# SI24r1.net
KiCad netlist of a schematic drawn in Altium Designer
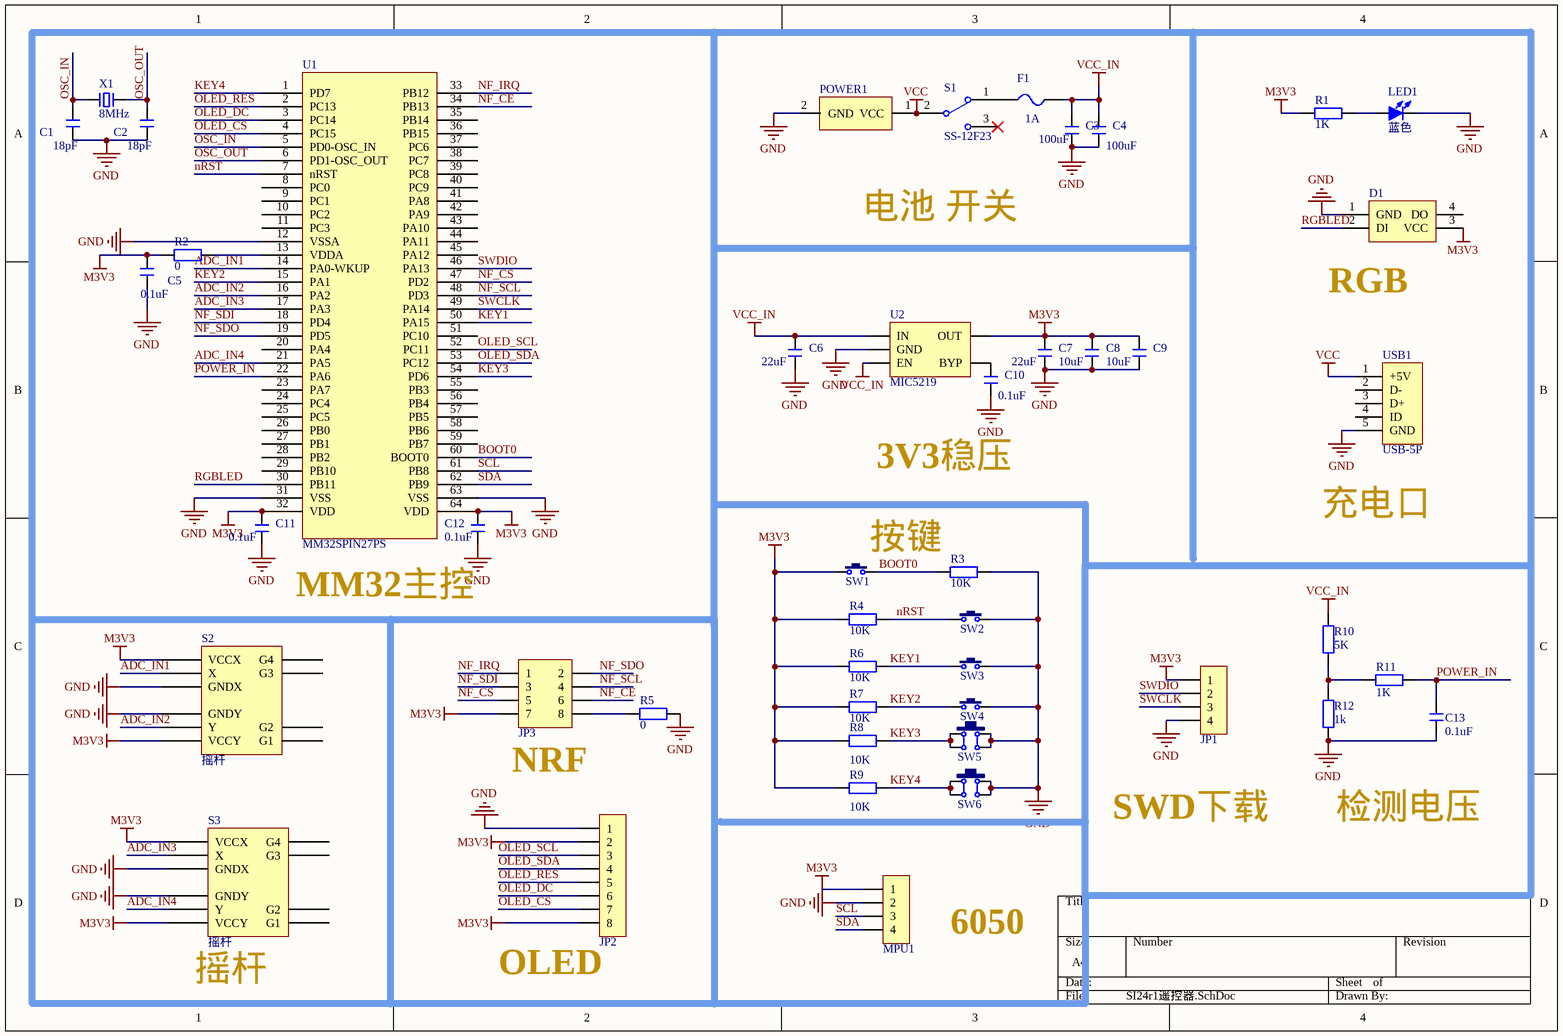
[diagram p0: SI24r1遥控器.SchDoc]

(export (version "E")
  (design (tool "Eeschema 10.0.6"))
  (components
    (comp (ref "C1")
      (value "18pF")
      (footprint "C 0805_M")
      (description "贴片电容")
      (libsource (lib "0.1 - 电阻-电容-电感") (part "C"))
    )
    (comp (ref "C2")
      (value "18pF")
      (footprint "C 0805_M")
      (description "贴片电容")
      (libsource (lib "0.1 - 电阻-电容-电感") (part "C"))
    )
    (comp (ref "C3")
      (value "100uF")
      (footprint "C 0805_M")
      (description "贴片电容")
      (libsource (lib "0.1 - 电阻-电容-电感") (part "C"))
    )
    (comp (ref "C4")
      (value "100uF")
      (footprint "C 0805_M")
      (description "贴片电容")
      (libsource (lib "0.1 - 电阻-电容-电感") (part "C"))
    )
    (comp (ref "C5")
      (value "0.1uF")
      (footprint "C 0805_M")
      (description "贴片电容")
      (libsource (lib "0.1 - 电阻-电容-电感") (part "C"))
    )
    (comp (ref "C6")
      (value "22uF")
      (footprint "C 0805_M")
      (description "贴片电容")
      (libsource (lib "0.1 - 电阻-电容-电感") (part "C"))
    )
    (comp (ref "C7")
      (value "22uF")
      (footprint "C 0805_M")
      (description "贴片电容")
      (libsource (lib "0.1 - 电阻-电容-电感") (part "C"))
    )
    (comp (ref "C8")
      (value "10uF")
      (footprint "C 0805_M")
      (description "贴片电容")
      (libsource (lib "0.1 - 电阻-电容-电感") (part "C"))
    )
    (comp (ref "C9")
      (value "10uF")
      (footprint "C 0805_M")
      (description "贴片电容")
      (libsource (lib "0.1 - 电阻-电容-电感") (part "C"))
    )
    (comp (ref "C10")
      (value "0.1uF")
      (footprint "C 0805_M")
      (description "贴片电容")
      (libsource (lib "0.1 - 电阻-电容-电感") (part "C"))
    )
    (comp (ref "C11")
      (value "0.1uF")
      (footprint "C 0805_M")
      (description "贴片电容")
      (libsource (lib "0.1 - 电阻-电容-电感") (part "C"))
    )
    (comp (ref "C12")
      (value "0.1uF")
      (footprint "C 0805_M")
      (description "贴片电容")
      (libsource (lib "0.1 - 电阻-电容-电感") (part "C"))
    )
    (comp (ref "C13")
      (value "0.1uF")
      (footprint "C 0805_M")
      (description "贴片电容")
      (libsource (lib "0.1 - 电阻-电容-电感") (part "C"))
    )
    (comp (ref "D1")
      (value "P923D")
      (footprint "RGB_LED_5050")
      (fields (field (name "PUBLISHER") "mazhongwei"))
      (libsource (lib "RoboFly") (part "P923D"))
    )
    (comp (ref "F1")
      (value "1A")
      (footprint "FU 0805")
      (description "贴片保险丝")
      (fields (field (name "版权归属") "源创客"))
      (libsource (lib "2.0 - 保险丝-晶振-光耦") (part "FU"))
    )
    (comp (ref "JP1")
      (value "HDR-1X4")
      (footprint "XH2.54-WI-4P")
      (description "4P接插件")
      (fields (field (name "版权归属") "封装库来自淘宝 ID：黄晶宝石"))
      (libsource (lib "5.3 - 接插件-脚距2.54 (100mil) ") (part "Header 4"))
    )
    (comp (ref "JP2")
      (value "HDR-1X8")
      (footprint "IPS")
      (description "8P接插件")
      (fields (field (name "版权归属") "封装库来自淘宝 ID：黄晶宝石"))
      (libsource (lib "5.3 - 接插件-脚距2.54 (100mil) ") (part "Header 8"))
    )
    (comp (ref "JP3")
      (value "Header 4X2")
      (footprint "HDR2.54-LI-2x4P")
      (description "4*2P接插件")
      (fields (field (name "版权归属") "封装库来自淘宝 ID：黄晶宝石"))
      (libsource (lib "5.3 - 接插件-脚距2.54 (100mil) ") (part "Header 4X2"))
    )
    (comp (ref "LED1")
      (value "蓝色")
      (footprint "LED 0805B")
      (description "贴片LED")
      (fields (field (name "版权归属") "封装库来自淘宝 ID：黄晶宝石"))
      (libsource (lib "0.3 - LED发光二极管") (part "LED-SMD"))
    )
    (comp (ref "MPU1")
      (value "HDR-1X4")
      (footprint "HDR2.54-LI-4P")
      (description "4P接插件")
      (fields (field (name "版权归属") "封装库来自淘宝 ID：黄晶宝石"))
      (libsource (lib "5.3 - 接插件-脚距2.54 (100mil) ") (part "Header 4"))
    )
    (comp (ref "POWER1") (value "~") (footprint "XH2.54-LI-2P") (libsource (lib "原理图库") (part "T槽")))
    (comp (ref "R1")
      (value "1K")
      (footprint "R 0805_M")
      (description "Resistor")
      (fields (field (name "Comment") "Res2") (field (name "PUBLISHER") "Altium Limited"))
      (libsource (lib "双电机节能车主板原理图库") (part "Res2"))
    )
    (comp (ref "R2") (value "0") (footprint "R 0805_M") (libsource (lib "") (part "RES_1")))
    (comp (ref "R3") (value "10K") (footprint "R 0805_M") (libsource (lib "飞思卡尔") (part "RES")))
    (comp (ref "R4") (value "10K") (footprint "R 0805_M") (libsource (lib "飞思卡尔") (part "RES")))
    (comp (ref "R5") (value "0") (footprint "R 0805_M") (libsource (lib "") (part "RES_1")))
    (comp (ref "R6") (value "10K") (footprint "R 0805_M") (libsource (lib "飞思卡尔") (part "RES")))
    (comp (ref "R7") (value "10K") (footprint "R 0805_M") (libsource (lib "飞思卡尔") (part "RES")))
    (comp (ref "R8") (value "10K") (footprint "R 0805_M") (libsource (lib "飞思卡尔") (part "RES")))
    (comp (ref "R9") (value "10K") (footprint "R 0805_M") (libsource (lib "飞思卡尔") (part "RES")))
    (comp (ref "R10")
      (value "5K")
      (footprint "R 0805_M")
      (description "Resistor")
      (fields (field (name "Comment") "Res2") (field (name "PUBLISHER") "Altium Limited"))
      (libsource (lib "") (part "Res2_1"))
    )
    (comp (ref "R11")
      (value "1K")
      (footprint "R 0805_M")
      (description "Resistor")
      (fields (field (name "Comment") "Res2") (field (name "PUBLISHER") "Altium Limited"))
      (libsource (lib "双电机节能车主板原理图库") (part "Res2"))
    )
    (comp (ref "R12")
      (value "1k")
      (footprint "R 0805_M")
      (description "Resistor")
      (fields (field (name "Comment") "Res2") (field (name "PUBLISHER") "Altium Limited"))
      (libsource (lib "") (part "Res2_1"))
    )
    (comp (ref "S1")
      (value "SS-12F23")
      (footprint "SS-12D10")
      (description "1路波动开关")
      (fields (field (name "版权归属") "封装库来自淘宝 ID：黄晶宝石"))
      (libsource (lib "0.7 - 常用按键-开关") (part "SSW-1P"))
    )
    (comp (ref "S2") (value "摇杆") (footprint "3D161摇杆") (libsource (lib "摇杆") (part "摇杆")))
    (comp (ref "S3") (value "摇杆") (footprint "3D161摇杆") (libsource (lib "摇杆") (part "摇杆")))
    (comp (ref "SW1")
      (value "3x6x5")
      (footprint "TSW SMD-3*6*2.5")
      (description "3x6轻触开关")
      (fields (field (name "版权归属") "封装库来自淘宝 ID：黄晶宝石"))
      (libsource (lib "0.7 - 常用按键-开关") (part "TSW 3x6"))
    )
    (comp (ref "SW2")
      (value "3x6x5")
      (footprint "TSW SMD-3*6*2.5")
      (description "3x6轻触开关")
      (fields (field (name "版权归属") "封装库来自淘宝 ID：黄晶宝石"))
      (libsource (lib "0.7 - 常用按键-开关") (part "TSW 3x6"))
    )
    (comp (ref "SW3")
      (value "6x6x5")
      (footprint "TSW DIP-6*6*7_V")
      (description "侧按直插6x6轻触开关")
      (fields (field (name "版权归属") "封装库来自淘宝 ID：黄晶宝石"))
      (libsource (lib "0.7 - 常用按键-开关") (part "TSW DIP-6x6_V"))
    )
    (comp (ref "SW4")
      (value "6x6x5")
      (footprint "TSW DIP-6*6*7_V")
      (description "侧按直插6x6轻触开关")
      (fields (field (name "版权归属") "封装库来自淘宝 ID：黄晶宝石"))
      (libsource (lib "0.7 - 常用按键-开关") (part "TSW DIP-6x6_V"))
    )
    (comp (ref "SW5")
      (value "6x6x5")
      (footprint "TSW DIP-6*6*6")
      (description "直插6x6轻触开关")
      (fields (field (name "版权归属") "封装库来自淘宝 ID：黄晶宝石"))
      (libsource (lib "0.7 - 常用按键-开关") (part "TSW DIP-6x6"))
    )
    (comp (ref "SW6")
      (value "6x6x5")
      (footprint "TSW DIP-6*6*6")
      (description "直插6x6轻触开关")
      (fields (field (name "版权归属") "封装库来自淘宝 ID：黄晶宝石"))
      (libsource (lib "0.7 - 常用按键-开关") (part "TSW DIP-6x6"))
    )
    (comp (ref "U1")
      (value "MM32SPIN27PS")
      (footprint "LQFP64 10x10_M")
      (libsource (lib "STC智能车") (part "MM32SPIN27PS"))
    )
    (comp (ref "U2") (value "MIC5219") (footprint "SOT23-5M") (libsource (lib "TI") (part "MIC5219")))
    (comp (ref "USB1")
      (value "USB-5P")
      (footprint "USB-MICRO_A")
      (description "微型USB母座")
      (libsource (lib "0.8 - 网口-音频插座") (part "USB-5P"))
    )
    (comp (ref "X1")
      (value "8MHz")
      (footprint "OSC 5032-2P")
      (description "2脚无源脚晶振")
      (fields (field (name "版权归属") "源创客"))
      (libsource (lib "2.0 - 保险丝-晶振-光耦") (part "XTAL-2P"))
    )
  )
  (nets
    (net (code "1") (name "/ADC_IN1") (class "Default")
      (node (ref "S2") (pin "2") (pinfunction "X_2") (pintype "passive"))
      (node (ref "U1") (pin "14") (pinfunction "PA0-WKUP_14") (pintype "passive"))
    )
    (net (code "2") (name "/ADC_IN2") (class "Default")
      (node (ref "S2") (pin "5") (pinfunction "Y_5") (pintype "passive"))
      (node (ref "U1") (pin "16") (pinfunction "PA2_16") (pintype "passive"))
    )
    (net (code "3") (name "/ADC_IN3") (class "Default")
      (node (ref "S3") (pin "2") (pinfunction "X_2") (pintype "passive"))
      (node (ref "U1") (pin "17") (pinfunction "PA3_17") (pintype "passive"))
    )
    (net (code "4") (name "/ADC_IN4") (class "Default")
      (node (ref "S3") (pin "5") (pinfunction "Y_5") (pintype "passive"))
      (node (ref "U1") (pin "21") (pinfunction "PA5_21") (pintype "passive"))
    )
    (net (code "5") (name "/BOOT0") (class "Default")
      (node (ref "R3") (pin "1") (pinfunction "1_1") (pintype "passive"))
      (node (ref "SW1") (pin "2") (pinfunction "2_2") (pintype "passive"))
      (node (ref "U1") (pin "60") (pinfunction "BOOT0_60") (pintype "passive"))
    )
    (net (code "6") (name "/KEY1") (class "Default")
      (node (ref "R6") (pin "2") (pinfunction "2_2") (pintype "passive"))
      (node (ref "SW3") (pin "1") (pinfunction "1_1") (pintype "passive"))
      (node (ref "U1") (pin "50") (pinfunction "PA15_50") (pintype "passive"))
    )
    (net (code "7") (name "/KEY2") (class "Default")
      (node (ref "R7") (pin "2") (pinfunction "2_2") (pintype "passive"))
      (node (ref "SW4") (pin "1") (pinfunction "1_1") (pintype "passive"))
      (node (ref "U1") (pin "15") (pinfunction "PA1_15") (pintype "passive"))
    )
    (net (code "8") (name "/KEY3") (class "Default")
      (node (ref "R8") (pin "2") (pinfunction "2_2") (pintype "passive"))
      (node (ref "SW5") (pin "1") (pinfunction "1_1") (pintype "passive"))
      (node (ref "SW5") (pin "4") (pinfunction "4_4") (pintype "passive"))
      (node (ref "U1") (pin "54") (pinfunction "PD6_54") (pintype "passive"))
    )
    (net (code "9") (name "/KEY4") (class "Default")
      (node (ref "R9") (pin "2") (pinfunction "2_2") (pintype "passive"))
      (node (ref "SW6") (pin "1") (pinfunction "1_1") (pintype "passive"))
      (node (ref "SW6") (pin "4") (pinfunction "4_4") (pintype "passive"))
      (node (ref "U1") (pin "1") (pinfunction "PD7_1") (pintype "passive"))
    )
    (net (code "10") (name "/NF_CE") (class "Default")
      (node (ref "JP3") (pin "6") (pinfunction "6_6") (pintype "passive"))
      (node (ref "U1") (pin "34") (pinfunction "PB13_34") (pintype "passive"))
    )
    (net (code "11") (name "/NF_CS") (class "Default")
      (node (ref "JP3") (pin "5") (pinfunction "5_5") (pintype "passive"))
      (node (ref "U1") (pin "47") (pinfunction "PD2_47") (pintype "passive"))
    )
    (net (code "12") (name "/NF_IRQ") (class "Default")
      (node (ref "JP3") (pin "1") (pinfunction "1_1") (pintype "passive"))
      (node (ref "U1") (pin "33") (pinfunction "PB12_33") (pintype "passive"))
    )
    (net (code "13") (name "/NF_SCL") (class "Default")
      (node (ref "JP3") (pin "4") (pinfunction "4_4") (pintype "passive"))
      (node (ref "U1") (pin "48") (pinfunction "PD3_48") (pintype "passive"))
    )
    (net (code "14") (name "/NF_SDI") (class "Default")
      (node (ref "JP3") (pin "3") (pinfunction "3_3") (pintype "passive"))
      (node (ref "U1") (pin "18") (pinfunction "PD4_18") (pintype "passive"))
    )
    (net (code "15") (name "/NF_SDO") (class "Default")
      (node (ref "JP3") (pin "2") (pinfunction "2_2") (pintype "passive"))
      (node (ref "U1") (pin "19") (pinfunction "PD5_19") (pintype "passive"))
    )
    (net (code "16") (name "/OLED_CS") (class "Default")
      (node (ref "JP2") (pin "7") (pinfunction "7_7") (pintype "passive"))
      (node (ref "U1") (pin "4") (pinfunction "PC15_4") (pintype "passive"))
    )
    (net (code "17") (name "/OLED_DC") (class "Default")
      (node (ref "JP2") (pin "6") (pinfunction "6_6") (pintype "passive"))
      (node (ref "U1") (pin "3") (pinfunction "PC14_3") (pintype "passive"))
    )
    (net (code "18") (name "/OLED_RES") (class "Default")
      (node (ref "JP2") (pin "5") (pinfunction "5_5") (pintype "passive"))
      (node (ref "U1") (pin "2") (pinfunction "PC13_2") (pintype "passive"))
    )
    (net (code "19") (name "/OLED_SCL") (class "Default")
      (node (ref "JP2") (pin "3") (pinfunction "3_3") (pintype "passive"))
      (node (ref "U1") (pin "52") (pinfunction "PC11_52") (pintype "passive"))
    )
    (net (code "20") (name "/OLED_SDA") (class "Default")
      (node (ref "JP2") (pin "4") (pinfunction "4_4") (pintype "passive"))
      (node (ref "U1") (pin "53") (pinfunction "PC12_53") (pintype "passive"))
    )
    (net (code "21") (name "/OSC_IN") (class "Default")
      (node (ref "C1") (pin "2") (pinfunction "2_2") (pintype "passive"))
      (node (ref "U1") (pin "5") (pinfunction "PD0-OSC_IN_5") (pintype "passive"))
      (node (ref "X1") (pin "1") (pinfunction "1_1") (pintype "passive"))
    )
    (net (code "22") (name "/OSC_OUT") (class "Default")
      (node (ref "C2") (pin "2") (pinfunction "2_2") (pintype "passive"))
      (node (ref "U1") (pin "6") (pinfunction "PD1-OSC_OUT_6") (pintype "passive"))
      (node (ref "X1") (pin "2") (pinfunction "2_2") (pintype "passive"))
    )
    (net (code "23") (name "/POWER_IN") (class "Default")
      (node (ref "C13") (pin "2") (pinfunction "2_2") (pintype "passive"))
      (node (ref "R11") (pin "1") (pinfunction "1_1") (pintype "passive"))
      (node (ref "U1") (pin "22") (pinfunction "PA6_22") (pintype "passive"))
    )
    (net (code "24") (name "/RGBLED") (class "Default")
      (node (ref "D1") (pin "2") (pinfunction "DI_2") (pintype "passive"))
      (node (ref "U1") (pin "30") (pinfunction "PB11_30") (pintype "passive"))
    )
    (net (code "25") (name "/SCL") (class "Default")
      (node (ref "MPU1") (pin "3") (pinfunction "3_3") (pintype "passive"))
      (node (ref "U1") (pin "61") (pinfunction "PB8_61") (pintype "passive"))
    )
    (net (code "26") (name "/SDA") (class "Default")
      (node (ref "MPU1") (pin "4") (pinfunction "4_4") (pintype "passive"))
      (node (ref "U1") (pin "62") (pinfunction "PB9_62") (pintype "passive"))
    )
    (net (code "27") (name "/SWCLK") (class "Default")
      (node (ref "JP1") (pin "3") (pinfunction "3_3") (pintype "passive"))
      (node (ref "U1") (pin "49") (pinfunction "PA14_49") (pintype "passive"))
    )
    (net (code "28") (name "/SWDIO") (class "Default")
      (node (ref "JP1") (pin "2") (pinfunction "2_2") (pintype "passive"))
      (node (ref "U1") (pin "46") (pinfunction "PA13_46") (pintype "passive"))
    )
    (net (code "29") (name "/nRST") (class "Default")
      (node (ref "R4") (pin "2") (pinfunction "2_2") (pintype "passive"))
      (node (ref "SW2") (pin "1") (pinfunction "1_1") (pintype "passive"))
      (node (ref "U1") (pin "7") (pinfunction "nRST_7") (pintype "passive"))
    )
    (net (code "30") (name "GND") (class "Default")
      (node (ref "C1") (pin "1") (pinfunction "1_1") (pintype "passive"))
      (node (ref "C10") (pin "1") (pinfunction "1_1") (pintype "passive"))
      (node (ref "C11") (pin "1") (pinfunction "1_1") (pintype "passive"))
      (node (ref "C12") (pin "1") (pinfunction "1_1") (pintype "passive"))
      (node (ref "C13") (pin "1") (pinfunction "1_1") (pintype "passive"))
      (node (ref "C2") (pin "1") (pinfunction "1_1") (pintype "passive"))
      (node (ref "C3") (pin "1") (pinfunction "1_1") (pintype "passive"))
      (node (ref "C4") (pin "1") (pinfunction "1_1") (pintype "passive"))
      (node (ref "C5") (pin "1") (pinfunction "1_1") (pintype "passive"))
      (node (ref "C6") (pin "1") (pinfunction "1_1") (pintype "passive"))
      (node (ref "C7") (pin "1") (pinfunction "1_1") (pintype "passive"))
      (node (ref "C8") (pin "1") (pinfunction "1_1") (pintype "passive"))
      (node (ref "C9") (pin "1") (pinfunction "1_1") (pintype "passive"))
      (node (ref "D1") (pin "1") (pinfunction "GND_1") (pintype "passive"))
      (node (ref "JP1") (pin "4") (pinfunction "4_4") (pintype "passive"))
      (node (ref "JP2") (pin "1") (pinfunction "1_1") (pintype "passive"))
      (node (ref "LED1") (pin "2") (pinfunction "K_2") (pintype "passive"))
      (node (ref "MPU1") (pin "2") (pinfunction "2_2") (pintype "passive"))
      (node (ref "POWER1") (pin "2") (pinfunction "GND_2") (pintype "passive"))
      (node (ref "R12") (pin "1") (pinfunction "1_1") (pintype "passive"))
      (node (ref "R3") (pin "2") (pinfunction "2_2") (pintype "passive"))
      (node (ref "R5") (pin "1") (pinfunction "1_1") (pintype "passive"))
      (node (ref "S2") (pin "3") (pinfunction "GNDX_3") (pintype "passive"))
      (node (ref "S2") (pin "4") (pinfunction "GNDY_4") (pintype "passive"))
      (node (ref "S3") (pin "3") (pinfunction "GNDX_3") (pintype "passive"))
      (node (ref "S3") (pin "4") (pinfunction "GNDY_4") (pintype "passive"))
      (node (ref "SW2") (pin "2") (pinfunction "2_2") (pintype "passive"))
      (node (ref "SW3") (pin "2") (pinfunction "2_2") (pintype "passive"))
      (node (ref "SW4") (pin "2") (pinfunction "2_2") (pintype "passive"))
      (node (ref "SW5") (pin "2") (pinfunction "2_2") (pintype "passive"))
      (node (ref "SW5") (pin "3") (pinfunction "3_3") (pintype "passive"))
      (node (ref "SW6") (pin "2") (pinfunction "2_2") (pintype "passive"))
      (node (ref "SW6") (pin "3") (pinfunction "3_3") (pintype "passive"))
      (node (ref "U1") (pin "12") (pinfunction "VSSA_12") (pintype "passive"))
      (node (ref "U1") (pin "31") (pinfunction "VSS_31") (pintype "passive"))
      (node (ref "U1") (pin "63") (pinfunction "VSS_63") (pintype "passive"))
      (node (ref "U2") (pin "2") (pinfunction "GND_2") (pintype "passive"))
      (node (ref "USB1") (pin "5") (pinfunction "GND_5") (pintype "passive"))
    )
    (net (code "31") (name "M3V3") (class "Default")
      (node (ref "C11") (pin "2") (pinfunction "2_2") (pintype "passive"))
      (node (ref "C12") (pin "2") (pinfunction "2_2") (pintype "passive"))
      (node (ref "C5") (pin "2") (pinfunction "2_2") (pintype "passive"))
      (node (ref "C7") (pin "2") (pinfunction "2_2") (pintype "passive"))
      (node (ref "C8") (pin "2") (pinfunction "2_2") (pintype "passive"))
      (node (ref "C9") (pin "2") (pinfunction "2_2") (pintype "passive"))
      (node (ref "D1") (pin "3") (pinfunction "VCC_3") (pintype "passive"))
      (node (ref "JP1") (pin "1") (pinfunction "1_1") (pintype "passive"))
      (node (ref "JP2") (pin "2") (pinfunction "2_2") (pintype "passive"))
      (node (ref "JP2") (pin "8") (pinfunction "8_8") (pintype "passive"))
      (node (ref "JP3") (pin "7") (pinfunction "7_7") (pintype "passive"))
      (node (ref "MPU1") (pin "1") (pinfunction "1_1") (pintype "passive"))
      (node (ref "R1") (pin "2") (pinfunction "2_2") (pintype "passive"))
      (node (ref "R2") (pin "2") (pinfunction "2_2") (pintype "passive"))
      (node (ref "R4") (pin "1") (pinfunction "1_1") (pintype "passive"))
      (node (ref "R6") (pin "1") (pinfunction "1_1") (pintype "passive"))
      (node (ref "R7") (pin "1") (pinfunction "1_1") (pintype "passive"))
      (node (ref "R8") (pin "1") (pinfunction "1_1") (pintype "passive"))
      (node (ref "R9") (pin "1") (pinfunction "1_1") (pintype "passive"))
      (node (ref "S2") (pin "1") (pinfunction "VCCX_1") (pintype "passive"))
      (node (ref "S2") (pin "6") (pinfunction "VCCY_6") (pintype "passive"))
      (node (ref "S3") (pin "1") (pinfunction "VCCX_1") (pintype "passive"))
      (node (ref "S3") (pin "6") (pinfunction "VCCY_6") (pintype "passive"))
      (node (ref "SW1") (pin "1") (pinfunction "1_1") (pintype "passive"))
      (node (ref "U1") (pin "32") (pinfunction "VDD_32") (pintype "passive"))
      (node (ref "U1") (pin "64") (pinfunction "VDD_64") (pintype "passive"))
      (node (ref "U2") (pin "5") (pinfunction "OUT_5") (pintype "passive"))
    )
    (net (code "32") (name "Net-(F1-Pad1)") (class "Default")
      (node (ref "F1") (pin "1") (pinfunction "1_1") (pintype "passive"))
      (node (ref "S1") (pin "1") (pinfunction "1_1") (pintype "passive"))
    )
    (net (code "33") (name "Net-(JP3-Pad8)") (class "Default")
      (node (ref "JP3") (pin "8") (pinfunction "8_8") (pintype "passive"))
      (node (ref "R5") (pin "2") (pinfunction "2_2") (pintype "passive"))
    )
    (net (code "34") (name "Net-(LED1-A)") (class "Default")
      (node (ref "LED1") (pin "1") (pinfunction "A_1") (pintype "passive"))
      (node (ref "R1") (pin "1") (pinfunction "1_1") (pintype "passive"))
    )
    (net (code "35") (name "Net-(R10-Pad1)") (class "Default")
      (node (ref "R10") (pin "1") (pinfunction "1_1") (pintype "passive"))
      (node (ref "R11") (pin "2") (pinfunction "2_2") (pintype "passive"))
      (node (ref "R12") (pin "2") (pinfunction "2_2") (pintype "passive"))
    )
    (net (code "36") (name "Net-(U1-VDDA)") (class "Default")
      (node (ref "R2") (pin "1") (pinfunction "1_1") (pintype "passive"))
      (node (ref "U1") (pin "13") (pinfunction "VDDA_13") (pintype "passive"))
    )
    (net (code "37") (name "Net-(U2-BYP)") (class "Default")
      (node (ref "C10") (pin "2") (pinfunction "2_2") (pintype "passive"))
      (node (ref "U2") (pin "4") (pinfunction "BYP_4") (pintype "passive"))
    )
    (net (code "38") (name "VCC") (class "Default")
      (node (ref "POWER1") (pin "1") (pinfunction "VCC_1") (pintype "passive"))
      (node (ref "S1") (pin "2") (pinfunction "2_2") (pintype "passive"))
      (node (ref "USB1") (pin "1") (pinfunction "+5V_1") (pintype "passive"))
    )
    (net (code "39") (name "VCC_IN") (class "Default")
      (node (ref "C3") (pin "2") (pinfunction "2_2") (pintype "passive"))
      (node (ref "C4") (pin "2") (pinfunction "2_2") (pintype "passive"))
      (node (ref "C6") (pin "2") (pinfunction "2_2") (pintype "passive"))
      (node (ref "F1") (pin "2") (pinfunction "2_2") (pintype "passive"))
      (node (ref "R10") (pin "2") (pinfunction "2_2") (pintype "passive"))
      (node (ref "U2") (pin "1") (pinfunction "IN_1") (pintype "passive"))
      (node (ref "U2") (pin "3") (pinfunction "EN_3") (pintype "passive"))
    )
    (net (code "40") (name "unconnected-(D1-DO-Pad4)") (class "Default")
      (node (ref "D1") (pin "4") (pinfunction "DO_4") (pintype "passive"))
    )
    (net (code "41") (name "unconnected-(S1-Pad3)") (class "Default")
      (node (ref "S1") (pin "3") (pinfunction "3_3") (pintype "passive+no_connect"))
    )
    (net (code "42") (name "unconnected-(S2-G1-Pad7)") (class "Default")
      (node (ref "S2") (pin "7") (pinfunction "G1_7") (pintype "passive"))
    )
    (net (code "43") (name "unconnected-(S2-G2-Pad8)") (class "Default")
      (node (ref "S2") (pin "8") (pinfunction "G2_8") (pintype "passive"))
    )
    (net (code "44") (name "unconnected-(S2-G3-Pad9)") (class "Default")
      (node (ref "S2") (pin "9") (pinfunction "G3_9") (pintype "passive"))
    )
    (net (code "45") (name "unconnected-(S2-G4-Pad10)") (class "Default")
      (node (ref "S2") (pin "10") (pinfunction "G4_10") (pintype "passive"))
    )
    (net (code "46") (name "unconnected-(S3-G1-Pad7)") (class "Default")
      (node (ref "S3") (pin "7") (pinfunction "G1_7") (pintype "passive"))
    )
    (net (code "47") (name "unconnected-(S3-G2-Pad8)") (class "Default")
      (node (ref "S3") (pin "8") (pinfunction "G2_8") (pintype "passive"))
    )
    (net (code "48") (name "unconnected-(S3-G3-Pad9)") (class "Default")
      (node (ref "S3") (pin "9") (pinfunction "G3_9") (pintype "passive"))
    )
    (net (code "49") (name "unconnected-(S3-G4-Pad10)") (class "Default")
      (node (ref "S3") (pin "10") (pinfunction "G4_10") (pintype "passive"))
    )
    (net (code "50") (name "unconnected-(U1-PA4-Pad20)") (class "Default")
      (node (ref "U1") (pin "20") (pinfunction "PA4_20") (pintype "passive"))
    )
    (net (code "51") (name "unconnected-(U1-PA7-Pad23)") (class "Default")
      (node (ref "U1") (pin "23") (pinfunction "PA7_23") (pintype "passive"))
    )
    (net (code "52") (name "unconnected-(U1-PA8-Pad41)") (class "Default")
      (node (ref "U1") (pin "41") (pinfunction "PA8_41") (pintype "passive"))
    )
    (net (code "53") (name "unconnected-(U1-PA9-Pad42)") (class "Default")
      (node (ref "U1") (pin "42") (pinfunction "PA9_42") (pintype "passive"))
    )
    (net (code "54") (name "unconnected-(U1-PA10-Pad43)") (class "Default")
      (node (ref "U1") (pin "43") (pinfunction "PA10_43") (pintype "passive"))
    )
    (net (code "55") (name "unconnected-(U1-PA11-Pad44)") (class "Default")
      (node (ref "U1") (pin "44") (pinfunction "PA11_44") (pintype "passive"))
    )
    (net (code "56") (name "unconnected-(U1-PA12-Pad45)") (class "Default")
      (node (ref "U1") (pin "45") (pinfunction "PA12_45") (pintype "passive"))
    )
    (net (code "57") (name "unconnected-(U1-PB0-Pad26)") (class "Default")
      (node (ref "U1") (pin "26") (pinfunction "PB0_26") (pintype "passive"))
    )
    (net (code "58") (name "unconnected-(U1-PB1-Pad27)") (class "Default")
      (node (ref "U1") (pin "27") (pinfunction "PB1_27") (pintype "passive"))
    )
    (net (code "59") (name "unconnected-(U1-PB2-Pad28)") (class "Default")
      (node (ref "U1") (pin "28") (pinfunction "PB2_28") (pintype "passive"))
    )
    (net (code "60") (name "unconnected-(U1-PB3-Pad55)") (class "Default")
      (node (ref "U1") (pin "55") (pinfunction "PB3_55") (pintype "passive"))
    )
    (net (code "61") (name "unconnected-(U1-PB4-Pad56)") (class "Default")
      (node (ref "U1") (pin "56") (pinfunction "PB4_56") (pintype "passive"))
    )
    (net (code "62") (name "unconnected-(U1-PB5-Pad57)") (class "Default")
      (node (ref "U1") (pin "57") (pinfunction "PB5_57") (pintype "passive"))
    )
    (net (code "63") (name "unconnected-(U1-PB6-Pad58)") (class "Default")
      (node (ref "U1") (pin "58") (pinfunction "PB6_58") (pintype "passive"))
    )
    (net (code "64") (name "unconnected-(U1-PB7-Pad59)") (class "Default")
      (node (ref "U1") (pin "59") (pinfunction "PB7_59") (pintype "passive"))
    )
    (net (code "65") (name "unconnected-(U1-PB10-Pad29)") (class "Default")
      (node (ref "U1") (pin "29") (pinfunction "PB10_29") (pintype "passive"))
    )
    (net (code "66") (name "unconnected-(U1-PB14-Pad35)") (class "Default")
      (node (ref "U1") (pin "35") (pinfunction "PB14_35") (pintype "passive"))
    )
    (net (code "67") (name "unconnected-(U1-PB15-Pad36)") (class "Default")
      (node (ref "U1") (pin "36") (pinfunction "PB15_36") (pintype "passive"))
    )
    (net (code "68") (name "unconnected-(U1-PC0-Pad8)") (class "Default")
      (node (ref "U1") (pin "8") (pinfunction "PC0_8") (pintype "passive"))
    )
    (net (code "69") (name "unconnected-(U1-PC1-Pad9)") (class "Default")
      (node (ref "U1") (pin "9") (pinfunction "PC1_9") (pintype "passive"))
    )
    (net (code "70") (name "unconnected-(U1-PC2-Pad10)") (class "Default")
      (node (ref "U1") (pin "10") (pinfunction "PC2_10") (pintype "passive"))
    )
    (net (code "71") (name "unconnected-(U1-PC3-Pad11)") (class "Default")
      (node (ref "U1") (pin "11") (pinfunction "PC3_11") (pintype "passive"))
    )
    (net (code "72") (name "unconnected-(U1-PC4-Pad24)") (class "Default")
      (node (ref "U1") (pin "24") (pinfunction "PC4_24") (pintype "passive"))
    )
    (net (code "73") (name "unconnected-(U1-PC5-Pad25)") (class "Default")
      (node (ref "U1") (pin "25") (pinfunction "PC5_25") (pintype "passive"))
    )
    (net (code "74") (name "unconnected-(U1-PC6-Pad37)") (class "Default")
      (node (ref "U1") (pin "37") (pinfunction "PC6_37") (pintype "passive"))
    )
    (net (code "75") (name "unconnected-(U1-PC7-Pad38)") (class "Default")
      (node (ref "U1") (pin "38") (pinfunction "PC7_38") (pintype "passive"))
    )
    (net (code "76") (name "unconnected-(U1-PC8-Pad39)") (class "Default")
      (node (ref "U1") (pin "39") (pinfunction "PC8_39") (pintype "passive"))
    )
    (net (code "77") (name "unconnected-(U1-PC9-Pad40)") (class "Default")
      (node (ref "U1") (pin "40") (pinfunction "PC9_40") (pintype "passive"))
    )
    (net (code "78") (name "unconnected-(U1-PC10-Pad51)") (class "Default")
      (node (ref "U1") (pin "51") (pinfunction "PC10_51") (pintype "passive"))
    )
    (net (code "79") (name "unconnected-(USB1-D+-Pad3)") (class "Default")
      (node (ref "USB1") (pin "3") (pinfunction "D+_3") (pintype "passive"))
    )
    (net (code "80") (name "unconnected-(USB1-D--Pad2)") (class "Default")
      (node (ref "USB1") (pin "2") (pinfunction "D-_2") (pintype "passive"))
    )
    (net (code "81") (name "unconnected-(USB1-ID-Pad4)") (class "Default")
      (node (ref "USB1") (pin "4") (pinfunction "ID_4") (pintype "passive"))
    )
  )
)
